# 1_ADSTM32-Power.net
KiCad netlist of a schematic drawn in Altium Designer
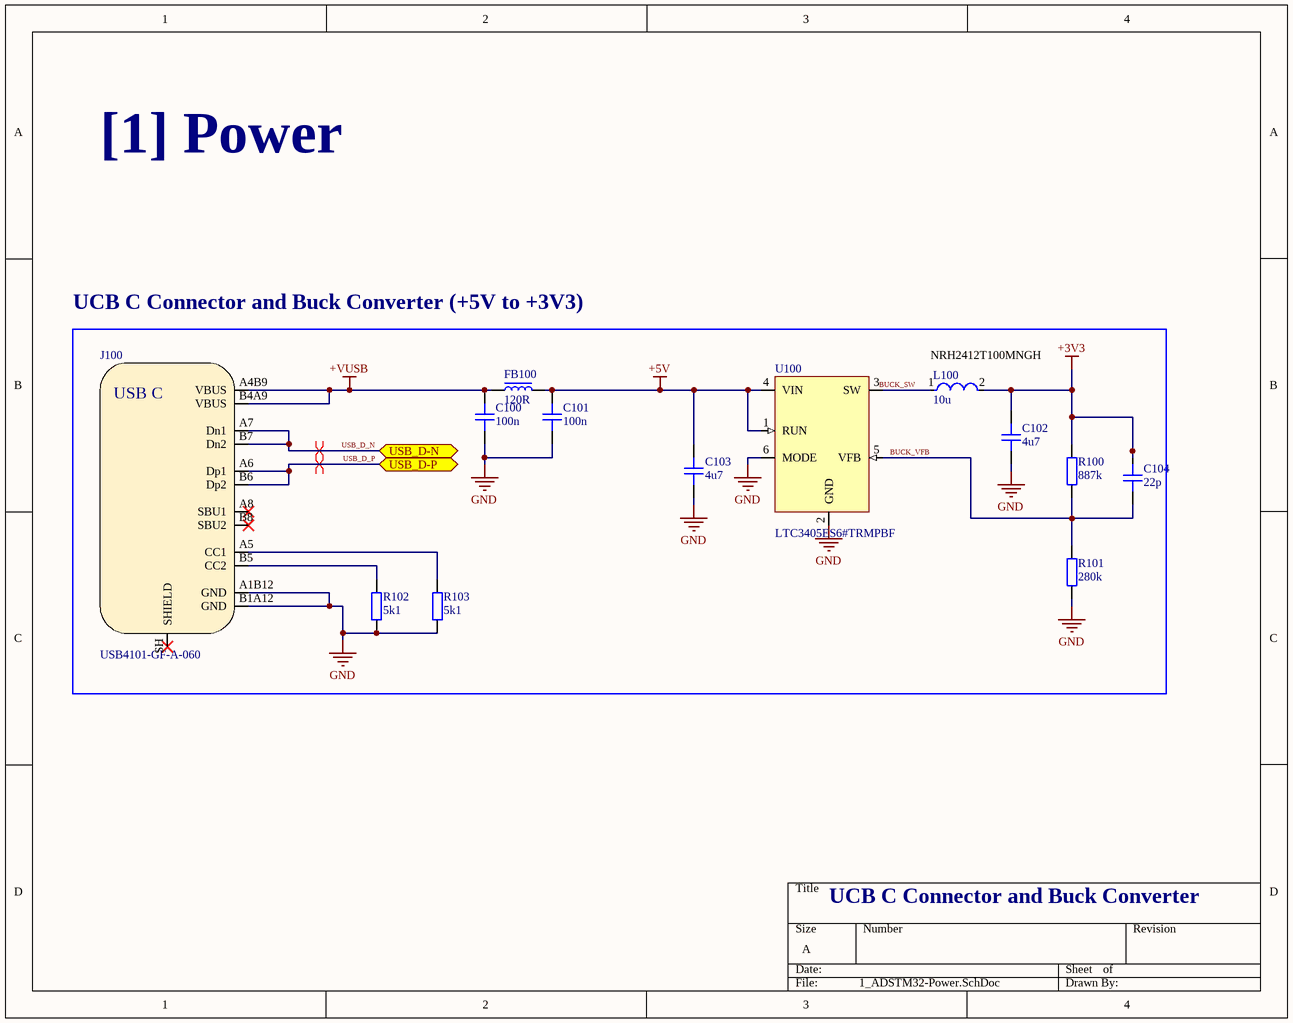
[diagram p0:  1_ADSTM32-Power.SchDoc]

(export (version "E")
  (design (tool "Eeschema 10.0.6"))
  (components
    (comp (ref "C100")
      (value "100n")
      (footprint "CAP_0603")
      (description "Capaictor SMD 0603 Generic")
      (libsource (lib "Schematic-Lib-KEM") (part "CAP_0603"))
    )
    (comp (ref "C101")
      (value "100n")
      (footprint "CAP_0603")
      (description "Capaictor SMD 0603 Generic")
      (libsource (lib "Schematic-Lib-KEM") (part "CAP_0603"))
    )
    (comp (ref "C102")
      (value "4u7")
      (footprint "CAP_0805")
      (description "Capacitor SMD 0805 Generic")
      (libsource (lib "Schematic-Lib-KEM") (part "CAP_0805_16V"))
    )
    (comp (ref "C103")
      (value "4u7")
      (footprint "CAP_0805")
      (description "Capacitor SMD 0805 Generic")
      (libsource (lib "Schematic-Lib-KEM") (part "CAP_0805_16V"))
    )
    (comp (ref "C104")
      (value "22p")
      (footprint "CAP_0603")
      (description "Capaictor SMD 0603 Generic")
      (libsource (lib "Schematic-Lib-KEM") (part "CAP_0603"))
    )
    (comp (ref "FB100")
      (value "120R")
      (footprint "FB_0603")
      (description "Ferrite Beads BMC-Q 0603 120R 25% Tol. High Current")
      (fields
        (field (name "MANUFACTURER") "Bourns")
        (field (name "MANUFACTURER PART NUMBER") "BMC-Q1JY0120H")
      )
      (libsource (lib "Schematic-Lib-KEM") (part "BMC-Q1JY0120H"))
    )
    (comp (ref "J100")
      (value "USB4101-GF-A-060")
      (footprint "USB4105-GF-A-060")
      (description "USB connector Type C SMT 12 pin")
      (fields
        (field (name "MANUFACTURER") "GCT")
        (field (name "MANUFACTURER PART NUMBER") "USB4105-GF-A-060")
      )
      (libsource (lib "Schematic-Lib-KEM") (part "USB4105-GF-A-060"))
    )
    (comp (ref "L100")
      (value "10u")
      (footprint "FP-NRH2412-MFG")
      (description "Shielded Wirewound Inductor 10uH 20% 0.51A 0.72Ω SMD")
      (fields (field (name "TOLERANCE") "20%"))
      (libsource (lib "Altium Content Vault") (part "725321dda6339637d4d059423bc1c3c"))
    )
    (comp (ref "R100")
      (value "887k")
      (footprint "RES_0603")
      (description "Resistor SMD 0603 Generic")
      (fields (field (name "TOLERANCE") "1%"))
      (libsource (lib "Schematic-Lib-KEM") (part "RES_0603"))
    )
    (comp (ref "R101")
      (value "280k")
      (footprint "RES_0603")
      (description "Resistor SMD 0603 Generic")
      (fields (field (name "TOLERANCE") "1%"))
      (libsource (lib "Schematic-Lib-KEM") (part "RES_0603"))
    )
    (comp (ref "R102")
      (value "5k1")
      (footprint "RES_0603")
      (description "Resistor SMD 0603 Generic")
      (libsource (lib "Schematic-Lib-KEM") (part "RES_0603"))
    )
    (comp (ref "R103")
      (value "5k1")
      (footprint "RES_0603")
      (description "Resistor SMD 0603 Generic")
      (libsource (lib "Schematic-Lib-KEM") (part "RES_0603"))
    )
    (comp (ref "U100")
      (value "LTC3405ES6#TRMPBF")
      (footprint "SOT-23-6")
      (description "1.5MHz, 300mA Synchronous Step-Down Regulator in ThinSOT")
      (fields (field (name "MANUFACTURER") "Analog Devices"))
      (libsource (lib "Schematic-Lib-KEM") (part "LTC3405ES6#TRMPBF"))
    )
  )
  (nets
    (net (code "1") (name "+3V3") (class "Default")
      (node (ref "C102") (pin "2") (pintype "passive"))
      (node (ref "C104") (pin "2") (pintype "passive"))
      (node (ref "L100") (pin "2") (pinfunction "2_2") (pintype "passive"))
      (node (ref "R100") (pin "2") (pintype "passive"))
    )
    (net (code "2") (name "+5V") (class "Default")
      (node (ref "C101") (pin "2") (pintype "passive"))
      (node (ref "C103") (pin "2") (pintype "passive"))
      (node (ref "FB100") (pin "2") (pintype "passive"))
      (node (ref "U100") (pin "1") (pinfunction "RUN_1") (pintype "input"))
      (node (ref "U100") (pin "4") (pinfunction "VIN_4") (pintype "power_in"))
    )
    (net (code "3") (name "+VUSB") (class "Default")
      (node (ref "C100") (pin "2") (pintype "passive"))
      (node (ref "FB100") (pin "1") (pintype "passive"))
      (node (ref "J100") (pin "A4B9") (pinfunction "VBUS_A4B9") (pintype "passive"))
      (node (ref "J100") (pin "B4A9") (pinfunction "VBUS_B4A9") (pintype "passive"))
    )
    (net (code "4") (name "/BUCK_SW") (class "Default")
      (node (ref "L100") (pin "1") (pinfunction "1_1") (pintype "passive"))
      (node (ref "U100") (pin "3") (pinfunction "SW_3") (pintype "power_in"))
    )
    (net (code "5") (name "/BUCK_VFB") (class "Default")
      (node (ref "C104") (pin "1") (pintype "passive"))
      (node (ref "R100") (pin "1") (pintype "passive"))
      (node (ref "R101") (pin "2") (pintype "passive"))
      (node (ref "U100") (pin "5") (pinfunction "VFB_5") (pintype "input"))
    )
    (net (code "6") (name "/USB_D_N") (class "Default")
      (node (ref "J100") (pin "A7") (pinfunction "Dn1_A7") (pintype "passive"))
      (node (ref "J100") (pin "B7") (pinfunction "Dn2_B7") (pintype "passive"))
    )
    (net (code "7") (name "/USB_D_P") (class "Default")
      (node (ref "J100") (pin "A6") (pinfunction "Dp1_A6") (pintype "passive"))
      (node (ref "J100") (pin "B6") (pinfunction "Dp2_B6") (pintype "passive"))
    )
    (net (code "8") (name "GND") (class "Default")
      (node (ref "C100") (pin "1") (pintype "passive"))
      (node (ref "C101") (pin "1") (pintype "passive"))
      (node (ref "C102") (pin "1") (pintype "passive"))
      (node (ref "C103") (pin "1") (pintype "passive"))
      (node (ref "J100") (pin "A1B12") (pinfunction "GND_A1B12") (pintype "passive"))
      (node (ref "J100") (pin "B1A12") (pinfunction "GND_B1A12") (pintype "passive"))
      (node (ref "R101") (pin "1") (pintype "passive"))
      (node (ref "R102") (pin "1") (pintype "passive"))
      (node (ref "R103") (pin "1") (pintype "passive"))
      (node (ref "U100") (pin "2") (pinfunction "GND_2") (pintype "power_in"))
      (node (ref "U100") (pin "6") (pinfunction "MODE_6") (pintype "passive"))
    )
    (net (code "9") (name "Net-(J100-CC1)") (class "Default")
      (node (ref "J100") (pin "A5") (pinfunction "CC1_A5") (pintype "passive"))
      (node (ref "R103") (pin "2") (pintype "passive"))
    )
    (net (code "10") (name "Net-(J100-CC2)") (class "Default")
      (node (ref "J100") (pin "B5") (pinfunction "CC2_B5") (pintype "passive"))
      (node (ref "R102") (pin "2") (pintype "passive"))
    )
    (net (code "11") (name "unconnected-(J100-SBU1-PadA8)") (class "Default")
      (node (ref "J100") (pin "A8") (pinfunction "SBU1_A8") (pintype "passive+no_connect"))
    )
    (net (code "12") (name "unconnected-(J100-SBU2-PadB8)") (class "Default")
      (node (ref "J100") (pin "B8") (pinfunction "SBU2_B8") (pintype "passive+no_connect"))
    )
    (net (code "13") (name "unconnected-(J100-SHIELD-PadSH)") (class "Default")
      (node (ref "J100") (pin "SH") (pinfunction "SHIELD_SH") (pintype "passive+no_connect"))
    )
  )
)
